# VIDEO_OUT_SVGA.net
KiCad netlist of a schematic drawn in Altium Designer
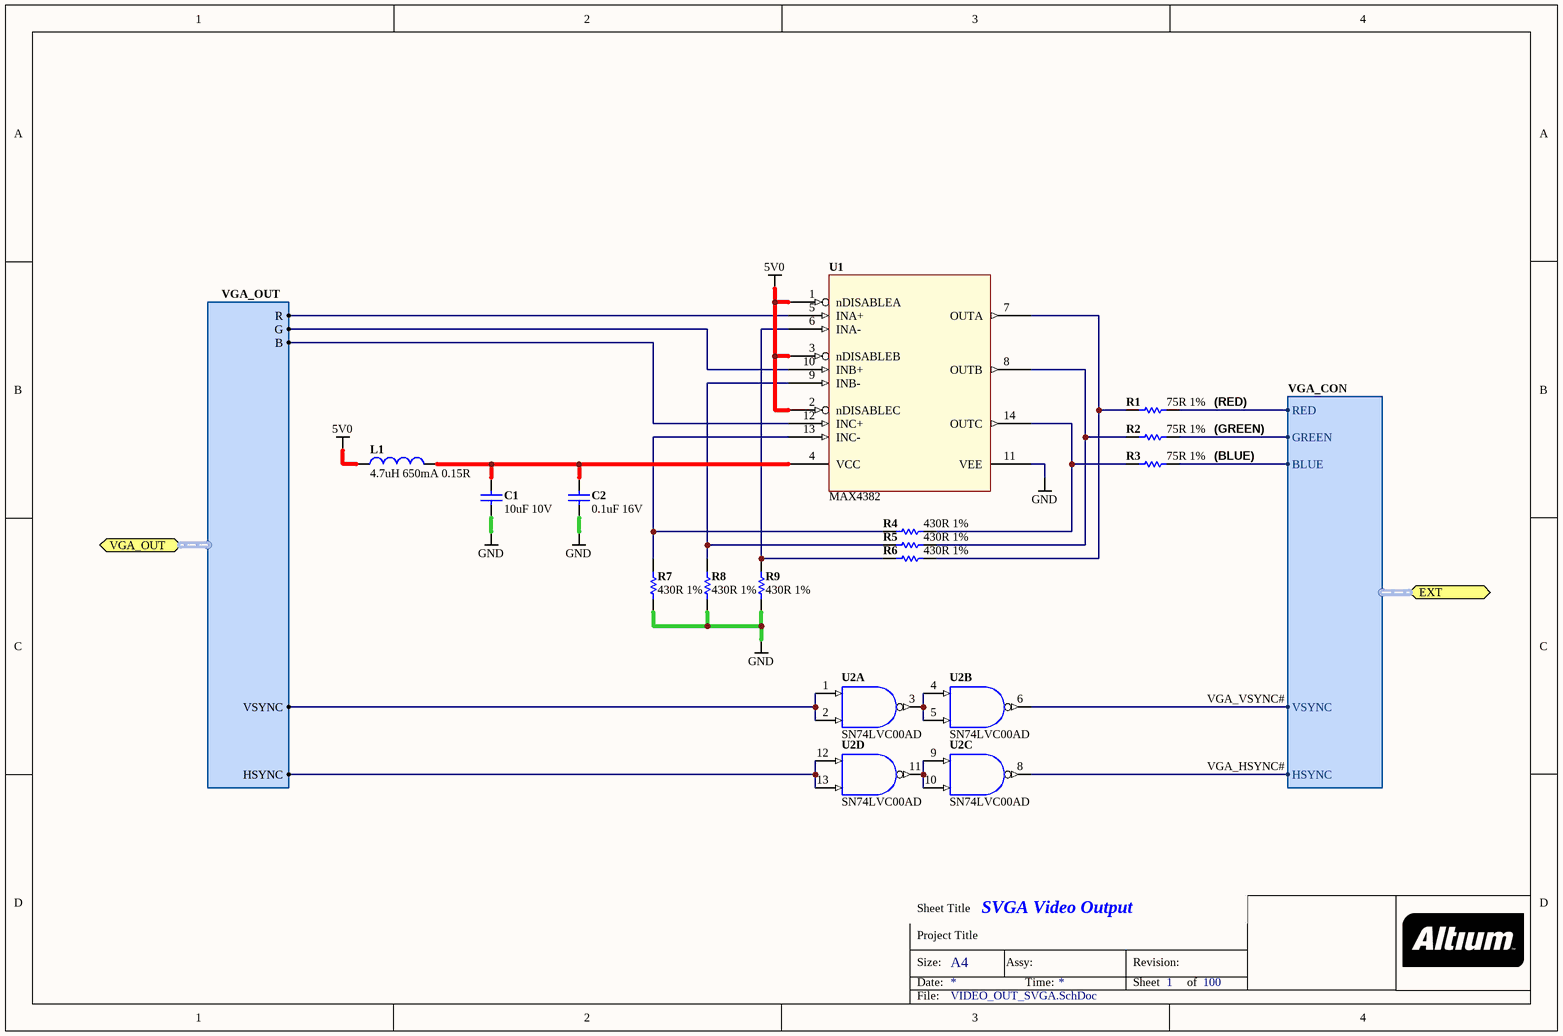
[diagram p0: VIDEO_OUT_SVGA.SchDoc]

(export (version "E")
  (design (tool "Eeschema 10.0.6"))
  (components
    (comp (ref "C1")
      (value "10uF 10V")
      (footprint "CAPC2012-STAR")
      (description "Capacitor, Ceramic, 10uF 10% 10V 0805 (2012) X5R")
      (fields (field (name "TOLERANCE") "10 %"))
      (libsource (lib "AltiumDesignLibrary") (part "CAP-NP"))
    )
    (comp (ref "C2")
      (value "0.1uF 16V")
      (footprint "CAPC1005-STAR")
      (description "Capacitor, Ceramic, 0.1uF 10% 16V 0402 (1005) X7R")
      (fields (field (name "TOLERANCE") "10 %"))
      (libsource (lib "AltiumDesignLibrary") (part "CAP-NP"))
    )
    (comp (ref "L1")
      (value "4.7uH 650mA 0.15R")
      (footprint "INDC3225")
      (description "Inductor, 4.7uH 650mA 0.15R 1210 (3225) LQH32CN4R7M11L")
      (libsource (lib "AltiumDesignLibrary") (part "IND"))
    )
    (comp (ref "R1")
      (value "75R 1%")
      (footprint "RESC1005-STAR")
      (description "Resistor, 75R 1% 0402")
      (fields (field (name "TOLERANCE") "1 %"))
      (libsource (lib "AltiumDesignLibrary") (part "RES"))
    )
    (comp (ref "R2")
      (value "75R 1%")
      (footprint "RESC1005-STAR")
      (description "Resistor, 75R 1% 0402")
      (fields (field (name "TOLERANCE") "1 %"))
      (libsource (lib "AltiumDesignLibrary") (part "RES"))
    )
    (comp (ref "R3")
      (value "75R 1%")
      (footprint "RESC1005-STAR")
      (description "Resistor, 75R 1% 0402")
      (fields (field (name "TOLERANCE") "1 %"))
      (libsource (lib "AltiumDesignLibrary") (part "RES"))
    )
    (comp (ref "R4")
      (value "430R 1%")
      (footprint "RESC1005-STAR")
      (description "Resistor, 430R 1% 0402 (1005)")
      (fields (field (name "TOLERANCE") "1 %"))
      (libsource (lib "AltiumDesignLibrary") (part "RES"))
    )
    (comp (ref "R5")
      (value "430R 1%")
      (footprint "RESC1005-STAR")
      (description "Resistor, 430R 1% 0402 (1005)")
      (fields (field (name "TOLERANCE") "1 %"))
      (libsource (lib "AltiumDesignLibrary") (part "RES"))
    )
    (comp (ref "R6")
      (value "430R 1%")
      (footprint "RESC1005-STAR")
      (description "Resistor, 430R 1% 0402 (1005)")
      (fields (field (name "TOLERANCE") "1 %"))
      (libsource (lib "AltiumDesignLibrary") (part "RES"))
    )
    (comp (ref "R7")
      (value "430R 1%")
      (footprint "RESC1005-STAR")
      (description "Resistor, 430R 1% 0402 (1005)")
      (fields (field (name "TOLERANCE") "1 %"))
      (libsource (lib "AltiumDesignLibrary") (part "RES"))
    )
    (comp (ref "R8")
      (value "430R 1%")
      (footprint "RESC1005-STAR")
      (description "Resistor, 430R 1% 0402 (1005)")
      (fields (field (name "TOLERANCE") "1 %"))
      (libsource (lib "AltiumDesignLibrary") (part "RES"))
    )
    (comp (ref "R9")
      (value "430R 1%")
      (footprint "RESC1005-STAR")
      (description "Resistor, 430R 1% 0402 (1005)")
      (fields (field (name "TOLERANCE") "1 %"))
      (libsource (lib "AltiumDesignLibrary") (part "RES"))
    )
    (comp (ref "U1")
      (value "MAX4382")
      (footprint "TSSOP-14")
      (description "MAX4382 OPAMP, TSSOP14")
      (libsource (lib "AltiumDesignLibrary") (part "MAX4382"))
    )
    (comp (ref "U2")
      (value "SN74LVC00AD")
      (footprint "SOIC127P600-14")
      (description "SN74LVC00AD, Quad 2-Input Positive-Nand Gates, 1.65-3.6V, 5V Tolerant Inputs")
      (libsource (lib "AltiumDesignLibrary") (part "SN74LVC00AD"))
    )
  )
  (nets
    (net (code "3") (name "/B") (class "Default")
      (node (ref "U1") (pin "12") (pinfunction "INC+_12") (pintype "input"))
    )
    (net (code "4") (name "/BLUE") (class "Default")
      (node (ref "R3") (pin "2") (pinfunction "2_2") (pintype "passive"))
    )
    (net (code "5") (name "/G") (class "Default")
      (node (ref "U1") (pin "10") (pinfunction "INB+_10") (pintype "input"))
    )
    (net (code "6") (name "/GREEN") (class "Default")
      (node (ref "R2") (pin "2") (pinfunction "2_2") (pintype "passive"))
    )
    (net (code "7") (name "/R") (class "Default")
      (node (ref "U1") (pin "5") (pinfunction "INA+_5") (pintype "input"))
    )
    (net (code "8") (name "/RED") (class "Default")
      (node (ref "R1") (pin "2") (pinfunction "2_2") (pintype "passive"))
    )
    (net (code "9") (name "/VGA_HSYNC#") (class "Default")
      (node (ref "U2") (pin "8") (pinfunction "Y_8") (pintype "output"))
    )
    (net (code "10") (name "/VGA_VSYNC#") (class "Default")
      (node (ref "U2") (pin "6") (pinfunction "Y_6") (pintype "output"))
    )
    (net (code "13") (name "5V0") (class "Default")
      (node (ref "L1") (pin "2") (pinfunction "2_2") (pintype "passive"))
      (node (ref "U1") (pin "1") (pinfunction "nDISABLEA_1") (pintype "input"))
      (node (ref "U1") (pin "2") (pinfunction "nDISABLEC_2") (pintype "input"))
      (node (ref "U1") (pin "3") (pinfunction "nDISABLEB_3") (pintype "input"))
    )
    (net (code "14") (name "GND") (class "Default")
      (node (ref "C1") (pin "1") (pinfunction "1_1") (pintype "passive"))
      (node (ref "C2") (pin "2") (pinfunction "2_2") (pintype "passive"))
      (node (ref "R7") (pin "1") (pinfunction "1_1") (pintype "passive"))
      (node (ref "R8") (pin "1") (pinfunction "1_1") (pintype "passive"))
      (node (ref "R9") (pin "1") (pinfunction "1_1") (pintype "passive"))
      (node (ref "U1") (pin "11") (pinfunction "VEE_11") (pintype "power_in"))
      (node (ref "U2") (pin "7") (pinfunction "GND_7") (pintype "power_in"))
    )
    (net (code "15") (name "Net-(U1-INA-)") (class "Default")
      (node (ref "R6") (pin "1") (pinfunction "1_1") (pintype "passive"))
      (node (ref "R9") (pin "2") (pinfunction "2_2") (pintype "passive"))
      (node (ref "U1") (pin "6") (pinfunction "INA-_6") (pintype "input"))
    )
    (net (code "16") (name "Net-(U1-INB-)") (class "Default")
      (node (ref "R5") (pin "1") (pinfunction "1_1") (pintype "passive"))
      (node (ref "R8") (pin "2") (pinfunction "2_2") (pintype "passive"))
      (node (ref "U1") (pin "9") (pinfunction "INB-_9") (pintype "input"))
    )
    (net (code "17") (name "Net-(U1-INC-)") (class "Default")
      (node (ref "R4") (pin "1") (pinfunction "1_1") (pintype "passive"))
      (node (ref "R7") (pin "2") (pinfunction "2_2") (pintype "passive"))
      (node (ref "U1") (pin "13") (pinfunction "INC-_13") (pintype "input"))
    )
    (net (code "18") (name "Net-(U1-OUTA)") (class "Default")
      (node (ref "R1") (pin "1") (pinfunction "1_1") (pintype "passive"))
      (node (ref "R6") (pin "2") (pinfunction "2_2") (pintype "passive"))
      (node (ref "U1") (pin "7") (pinfunction "OUTA_7") (pintype "output"))
    )
    (net (code "19") (name "Net-(U1-OUTB)") (class "Default")
      (node (ref "R2") (pin "1") (pinfunction "1_1") (pintype "passive"))
      (node (ref "R5") (pin "2") (pinfunction "2_2") (pintype "passive"))
      (node (ref "U1") (pin "8") (pinfunction "OUTB_8") (pintype "output"))
    )
    (net (code "20") (name "Net-(U1-OUTC)") (class "Default")
      (node (ref "R3") (pin "1") (pinfunction "1_1") (pintype "passive"))
      (node (ref "R4") (pin "2") (pinfunction "2_2") (pintype "passive"))
      (node (ref "U1") (pin "14") (pinfunction "OUTC_14") (pintype "output"))
    )
    (net (code "21") (name "Net-(U1-VCC)") (class "Default")
      (node (ref "C1") (pin "2") (pinfunction "2_2") (pintype "passive"))
      (node (ref "C2") (pin "1") (pinfunction "1_1") (pintype "passive"))
      (node (ref "L1") (pin "1") (pinfunction "1_1") (pintype "passive"))
      (node (ref "U1") (pin "4") (pinfunction "VCC_4") (pintype "power_in"))
    )
    (net (code "22") (name "Net-(U2A-A)") (class "Default")
      (node (ref "U2") (pin "1") (pinfunction "A_1") (pintype "input"))
      (node (ref "U2") (pin "2") (pinfunction "B_2") (pintype "input"))
    )
    (net (code "23") (name "Net-(U2A-Y)") (class "Default")
      (node (ref "U2") (pin "3") (pinfunction "Y_3") (pintype "output"))
      (node (ref "U2") (pin "4") (pinfunction "A_4") (pintype "input"))
      (node (ref "U2") (pin "5") (pinfunction "B_5") (pintype "input"))
    )
    (net (code "24") (name "Net-(U2C-A)") (class "Default")
      (node (ref "U2") (pin "10") (pinfunction "B_10") (pintype "input"))
      (node (ref "U2") (pin "11") (pinfunction "Y_11") (pintype "output"))
      (node (ref "U2") (pin "9") (pinfunction "A_9") (pintype "input"))
    )
    (net (code "25") (name "Net-(U2D-A)") (class "Default")
      (node (ref "U2") (pin "12") (pinfunction "A_12") (pintype "input"))
      (node (ref "U2") (pin "13") (pinfunction "B_13") (pintype "input"))
    )
    (net (code "26") (name "VDD") (class "Default")
      (node (ref "U2") (pin "14") (pinfunction "VDD_14") (pintype "power_in"))
    )
  )
)
